# M2.net
KiCad netlist of a schematic drawn in Altium Designer
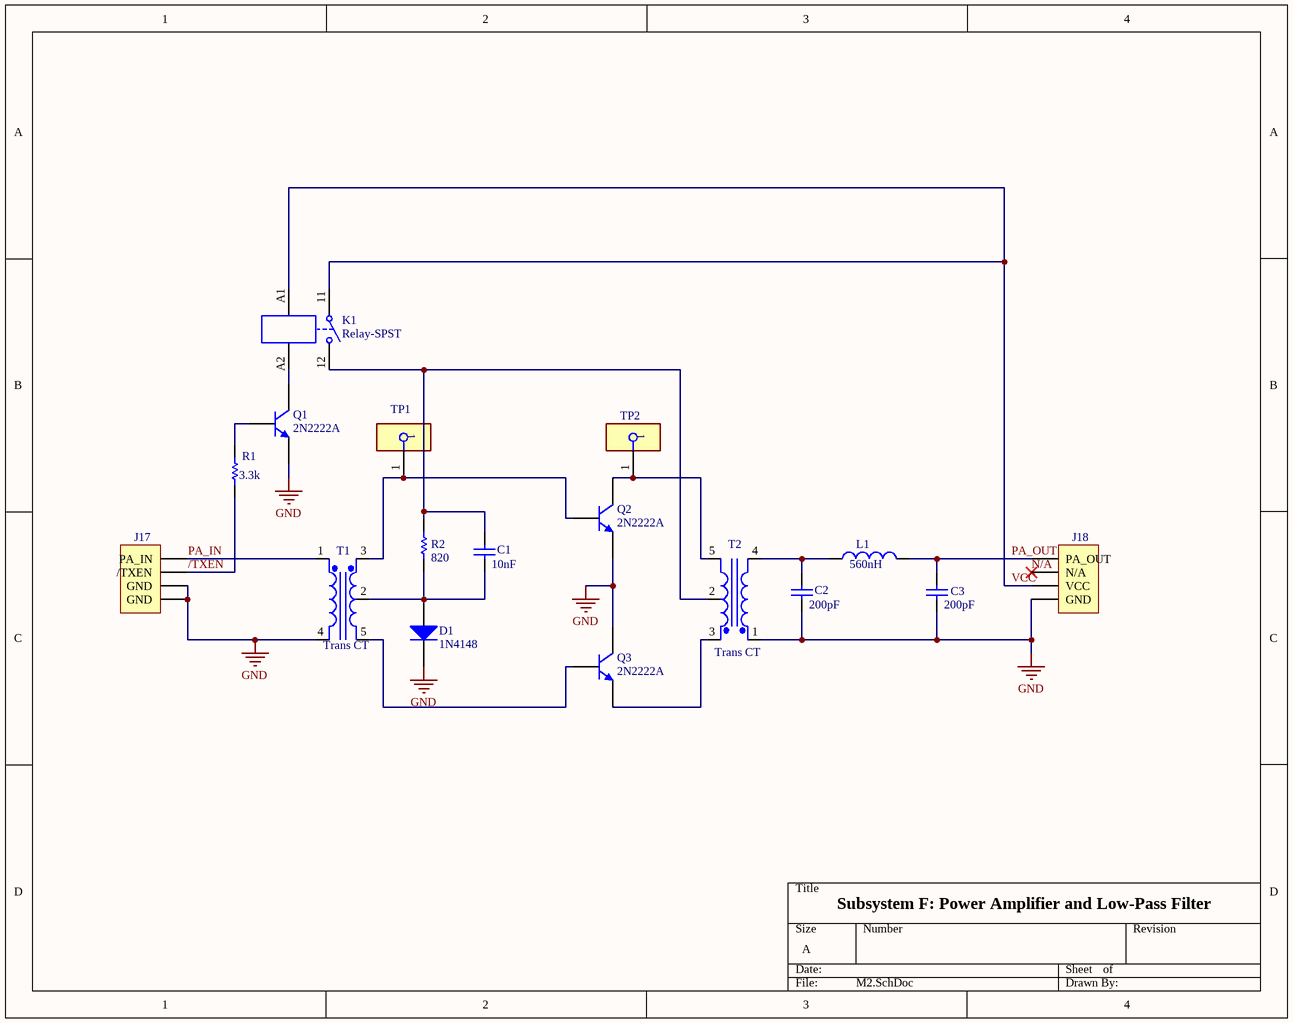
[diagram p0: M2.SchDoc]

(export (version "E")
  (design (tool "Eeschema 10.0.6"))
  (components
    (comp (ref "C1")
      (value "10nF")
      (footprint "RADIAL-0.1")
      (description "Capacitor")
      (fields
        (field (name "MANUFACTURER PART NUMBER") "C317C103M5U5TA")
        (field (name "Comment") "Cap")
        (field (name "PUBLISHER") "Altium Limited")
      )
      (libsource (lib "Capacitors-TH$") (part "CAP CER 10000PF 50V Z5U RADIAL"))
    )
    (comp (ref "C2")
      (value "200pF")
      (footprint "RADIAL-0.1")
      (description "Capacitor")
      (fields
        (field (name "MANUFACTURER PART NUMBER") "K101K15C0GF53L2")
        (field (name "Comment") "Cap")
        (field (name "PUBLISHER") "Altium Limited")
      )
      (libsource (lib "Capacitors-TH$") (part "CAP CER 100PF 50V C0G/NP0 RADIAL"))
    )
    (comp (ref "C3")
      (value "C3")
      (footprint "RADIAL-0.1")
      (description "Capacitor")
      (fields
        (field (name "ALTIUM_VALUE") "200pF")
        (field (name "MANUFACTURER PART NUMBER") "K101K15C0GF53L2")
        (field (name "PUBLISHER") "Altium Limited")
      )
      (libsource (lib "Capacitors-TH$") (part "CAP CER 100PF 50V C0G/NP0 RADIAL"))
    )
    (comp (ref "D1")
      (value "1N4148")
      (footprint "DO-35")
      (description "High Conductance Fast Diode")
      (fields (field (name "PUBLISHER") "Altium Limited"))
      (libsource (lib "Miscellaneous Devices") (part "Diode 1N4148"))
    )
    (comp (ref "J17")
      (value "Header 4")
      (footprint "HDR1X4")
      (description "Header, 4-Pin")
      (fields (field (name "PUBLISHER") "Altium Limited"))
      (libsource (lib "Miscellaneous Connectors") (part "Header 4"))
    )
    (comp (ref "J18")
      (value "Header 4")
      (footprint "HDR1X4")
      (description "Header, 4-Pin")
      (fields (field (name "PUBLISHER") "Altium Limited"))
      (libsource (lib "") (part "Header 4_1"))
    )
    (comp (ref "K1")
      (value "Relay-SPST")
      (footprint "Relay:PCBComponent_1")
      (description "Single-Pole Single-Throw Relay")
      (fields (field (name "PUBLISHER") "Altium Limited"))
      (libsource (lib "Miscellaneous Devices") (part "Relay-SPST"))
    )
    (comp (ref "L1")
      (value "560nH")
      (footprint "New Inductor")
      (description "Ind RF Choke Bobbin Core 560nH 10% 25MHz 40Q-Factor Ferrite 950mA AXL Bag")
      (fields
        (field (name "MANUFACTURER") "TDK")
        (field (name "MANUFACTURER PART NUMBER") "MLF1608DR56K")
        (field (name "PUBLISHER") "Altium Limited")
      )
      (libsource (lib "Miscellaneous Devices") (part "Inductor"))
    )
    (comp (ref "Q1")
      (value "2N2222A")
      (footprint "TO127P584H533-3")
      (description "High Speed Switch, 0.6 A IC, -65 to 175 degC, 3-Pin TO-18, RoHS, Bulk")
      (fields (field (name "MANUFACTURER") "STMicroelectronics"))
      (libsource (lib "Other$") (part "CMP-2000-05381-1"))
    )
    (comp (ref "Q2")
      (value "2N2222A")
      (footprint "TO127P584H533-3")
      (description "High Speed Switch, 0.6 A IC, -65 to 175 degC, 3-Pin TO-18, RoHS, Bulk")
      (fields (field (name "MANUFACTURER") "STMicroelectronics"))
      (libsource (lib "Other$") (part "CMP-2000-05381-1"))
    )
    (comp (ref "Q3")
      (value "2N2222A")
      (footprint "SnapEDApcb:TO127P584H533-3")
      (description "High Speed Switch, 0.6 A IC, -65 to 175 degC, 3-Pin TO-18, RoHS, Bulk")
      (fields (field (name "MANUFACTURER") "STMicroelectronics"))
      (libsource (lib "Other$") (part "CMP-2000-05381-1"))
    )
    (comp (ref "R1")
      (value "3.3k")
      (footprint "AXIAL-0.1-RES")
      (description "Resistor")
      (fields
        (field (name "MANUFACTURER PART NUMBER") "CFR-25JB-52-1K")
        (field (name "TOLERANCE") "0.05")
        (field (name "PUBLISHER") "Altium Limited")
      )
      (libsource (lib "ECE295-Resistors-TH") (part "RES 1K OHM 5% 1/4W AXIAL"))
    )
    (comp (ref "R2")
      (value "R2")
      (footprint "AXIAL-0.1-RES")
      (description "Resistor")
      (fields
        (field (name "ALTIUM_VALUE") "820")
        (field (name "MANUFACTURER PART NUMBER") "CFR-25JB-52-820R")
        (field (name "TOLERANCE") "0.05")
        (field (name "PUBLISHER") "Altium Limited")
      )
      (libsource (lib "ECE295-Resistors-TH") (part "RES 820 OHM 5% 1/4W AXIAL"))
    )
    (comp (ref "T1")
      (value "Trans CT")
      (footprint "BIFILAR-2402")
      (description "Common Mode Chokes / Filters WE-SL 100uH 700mA DCR=100mOhms")
      (fields
        (field (name "MANUFACTURER") "Wurth Electronics")
        (field (name "MANUFACTURER PART NUMBER") "744205")
        (field (name "PUBLISHER") "Altium Limited")
      )
      (libsource (lib "Miscellaneous Devices") (part "Trans CT"))
    )
    (comp (ref "T2")
      (value "Trans CT")
      (footprint "BIFILAR-2402")
      (description "Common Mode Chokes / Filters WE-SL 100uH 700mA DCR=100mOhms")
      (fields
        (field (name "MANUFACTURER") "Wurth Electronics")
        (field (name "MANUFACTURER PART NUMBER") "744205")
        (field (name "PUBLISHER") "Altium Limited")
      )
      (libsource (lib "Miscellaneous Devices") (part "Trans CT"))
    )
    (comp (ref "TP1")
      (value "5006")
      (footprint "FP-5006-MFG")
      (description "PC TEST POINT COMPACT BLACK")
      (libsource (lib "Altium Content Vault") (part "98815daf2f2c152b0c43f5ab9800df6"))
    )
    (comp (ref "TP2")
      (value "5006")
      (footprint "FP-5006-MFG")
      (description "PC TEST POINT COMPACT BLACK")
      (libsource (lib "Altium Content Vault") (part "98815daf2f2c152b0c43f5ab9800df6"))
    )
  )
  (nets
    (net (code "1") (name "/N{slash}A") (class "Default")
      (node (ref "J18") (pin "2") (pinfunction "N/A_2") (pintype "passive+no_connect"))
    )
    (net (code "2") (name "/PA_IN") (class "Default")
      (node (ref "J17") (pin "1") (pinfunction "PA_IN_1") (pintype "passive"))
      (node (ref "T1") (pin "1") (pinfunction "Pri+_1") (pintype "passive"))
    )
    (net (code "3") (name "/PA_OUT") (class "Default")
      (node (ref "C3") (pin "2") (pinfunction "2_2") (pintype "passive"))
      (node (ref "J18") (pin "1") (pinfunction "PA_OUT_1") (pintype "passive"))
      (node (ref "L1") (pin "2") (pinfunction "2_2") (pintype "passive"))
    )
    (net (code "4") (name "/VCC") (class "Default")
      (node (ref "J18") (pin "3") (pinfunction "VCC_3") (pintype "passive"))
      (node (ref "K1") (pin "11") (pinfunction "1_11") (pintype "passive"))
      (node (ref "K1") (pin "A1") (pinfunction "3_A1") (pintype "passive"))
    )
    (net (code "5") (name "/{slash}TXEN") (class "Default")
      (node (ref "J17") (pin "2") (pinfunction "/TXEN_2") (pintype "passive"))
      (node (ref "R1") (pin "2") (pinfunction "2_2") (pintype "passive"))
    )
    (net (code "6") (name "GND") (class "Default")
      (node (ref "C2") (pin "1") (pinfunction "1_1") (pintype "passive"))
      (node (ref "C3") (pin "1") (pinfunction "1_1") (pintype "passive"))
      (node (ref "D1") (pin "2") (pinfunction "K_2") (pintype "passive"))
      (node (ref "J17") (pin "3") (pinfunction "GND_3") (pintype "passive"))
      (node (ref "J17") (pin "4") (pinfunction "GND_4") (pintype "passive"))
      (node (ref "J18") (pin "4") (pinfunction "GND_4") (pintype "passive"))
      (node (ref "Q1") (pin "3") (pinfunction "E_3") (pintype "passive"))
      (node (ref "Q2") (pin "3") (pinfunction "E_3") (pintype "passive"))
      (node (ref "Q3") (pin "2") (pinfunction "C_2") (pintype "passive"))
      (node (ref "T1") (pin "4") (pinfunction "Pri-_4") (pintype "passive"))
      (node (ref "T2") (pin "1") (pinfunction "Pri+_1") (pintype "passive"))
    )
    (net (code "7") (name "Net-(D1-A)") (class "Default")
      (node (ref "C1") (pin "1") (pinfunction "1_1") (pintype "passive"))
      (node (ref "D1") (pin "1") (pinfunction "A_1") (pintype "passive"))
      (node (ref "R2") (pin "1") (pinfunction "1_1") (pintype "passive"))
      (node (ref "T1") (pin "2") (pinfunction "SecCT_2") (pintype "passive"))
    )
    (net (code "8") (name "Net-(K1-2)") (class "Default")
      (node (ref "C1") (pin "2") (pinfunction "2_2") (pintype "passive"))
      (node (ref "K1") (pin "12") (pinfunction "2_12") (pintype "passive"))
      (node (ref "R2") (pin "2") (pinfunction "2_2") (pintype "passive"))
      (node (ref "T2") (pin "2") (pinfunction "SecCT_2") (pintype "passive"))
    )
    (net (code "9") (name "Net-(K1-4)") (class "Default")
      (node (ref "K1") (pin "A2") (pinfunction "4_A2") (pintype "passive"))
      (node (ref "Q1") (pin "2") (pinfunction "C_2") (pintype "passive"))
    )
    (net (code "10") (name "Net-(Q1-B)") (class "Default")
      (node (ref "Q1") (pin "1") (pinfunction "B_1") (pintype "passive"))
      (node (ref "R1") (pin "1") (pinfunction "1_1") (pintype "passive"))
    )
    (net (code "11") (name "Net-(Q2-B)") (class "Default")
      (node (ref "Q2") (pin "1") (pinfunction "B_1") (pintype "passive"))
      (node (ref "T1") (pin "3") (pinfunction "Sec+_3") (pintype "passive"))
      (node (ref "TP1") (pin "1") (pinfunction "1_1") (pintype "passive"))
    )
    (net (code "12") (name "Net-(Q2-C)") (class "Default")
      (node (ref "Q2") (pin "2") (pinfunction "C_2") (pintype "passive"))
      (node (ref "T2") (pin "5") (pinfunction "Sec-_5") (pintype "passive"))
      (node (ref "TP2") (pin "1") (pinfunction "1_1") (pintype "passive"))
    )
    (net (code "13") (name "Net-(Q3-B)") (class "Default")
      (node (ref "Q3") (pin "1") (pinfunction "B_1") (pintype "passive"))
      (node (ref "T1") (pin "5") (pinfunction "Sec-_5") (pintype "passive"))
    )
    (net (code "14") (name "Net-(Q3-E)") (class "Default")
      (node (ref "Q3") (pin "3") (pinfunction "E_3") (pintype "passive"))
      (node (ref "T2") (pin "3") (pinfunction "Sec+_3") (pintype "passive"))
    )
    (net (code "15") (name "Net-(T2-Pri-)") (class "Default")
      (node (ref "C2") (pin "2") (pinfunction "2_2") (pintype "passive"))
      (node (ref "L1") (pin "1") (pinfunction "1_1") (pintype "passive"))
      (node (ref "T2") (pin "4") (pinfunction "Pri-_4") (pintype "passive"))
    )
  )
)
